# Loop_Schematic_r1_1_easyeda.net
KiCad netlist of a schematic drawn in EasyEDA
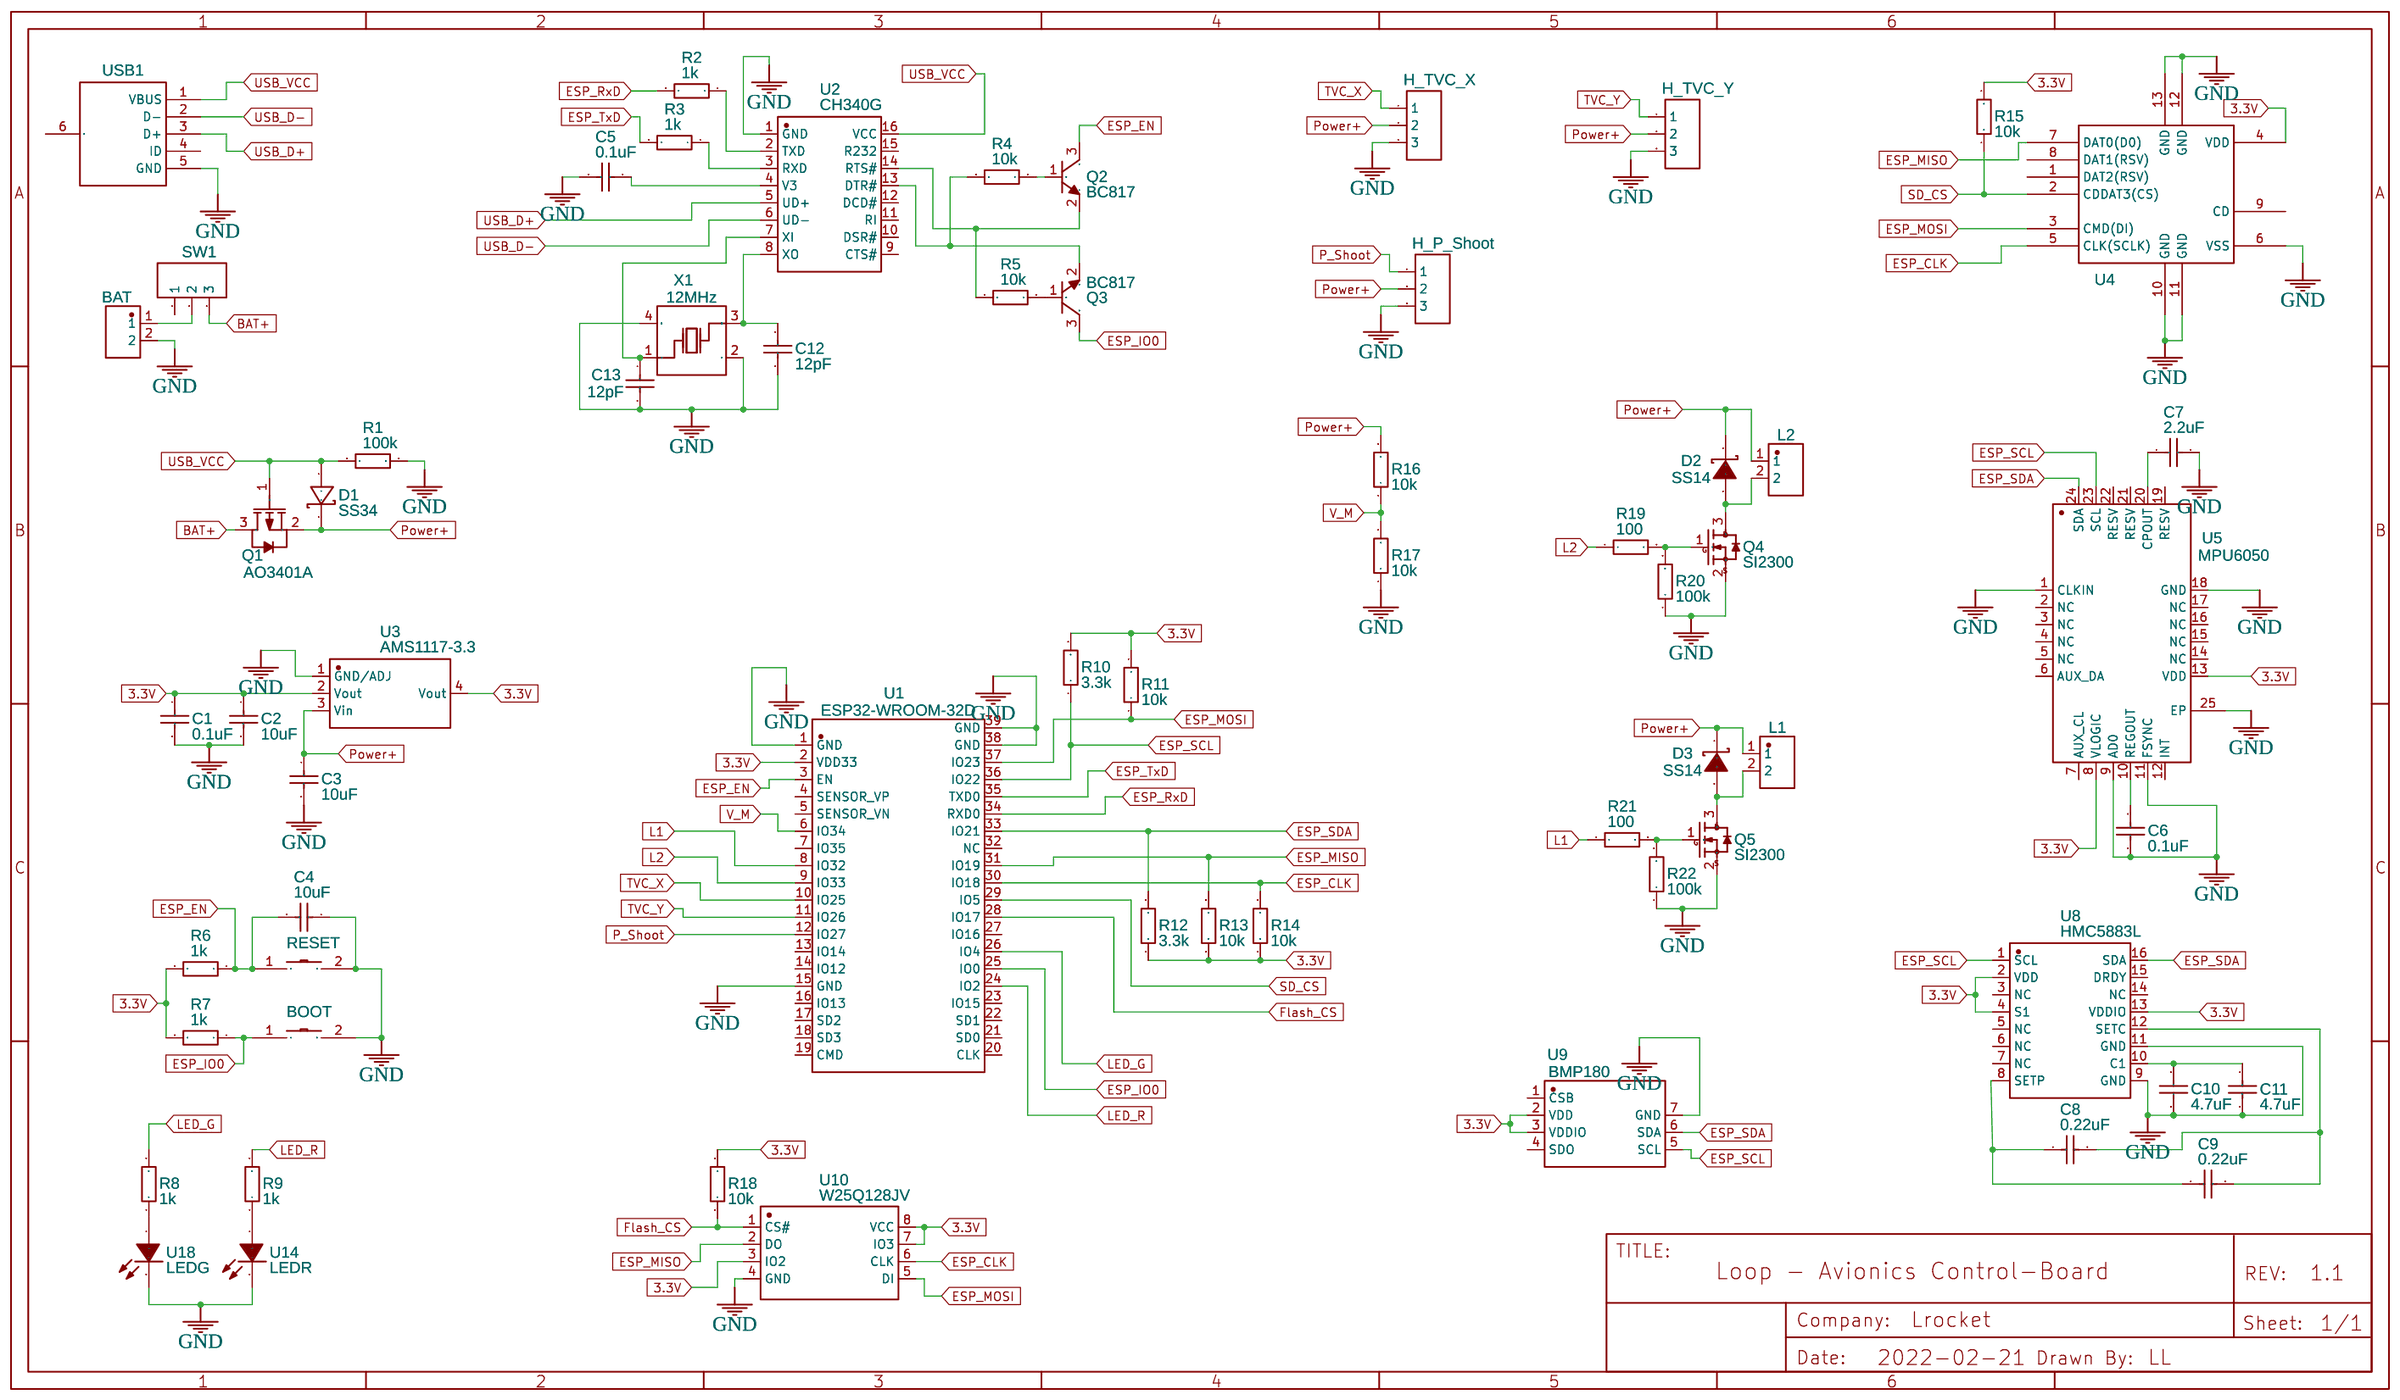
[diagram p0: schematic sheet]

(export (version "E")
  (design (tool "Eeschema 10.0.6"))
  (components
    (comp (ref "BAT")
      (value "XY308-2.54-2P")
      (fields (field (name "BOM_Supplier Part") "C557685"))
      (libsource (lib "") (part "XY308-2.54-2P_1"))
    )
    (comp (ref "BOOT")
      (value "TS-1101-C-W")
      (fields (field (name "BOM_Supplier Part") "C318938"))
      (libsource (lib "") (part "TS-1101-C-W_1"))
    )
    (comp (ref "C1")
      (value "0.1uF")
      (fields
        (field (name "BOM_Manufacturer Part") "CC0603KRX7R9BB103")
        (field (name "BOM_Supplier Part") "C100042")
      )
      (libsource (lib "") (part "CC0603KRX7R9BB103"))
    )
    (comp (ref "C2")
      (value "10uF")
      (fields
        (field (name "BOM_Manufacturer Part") "CC0603KRX7R9BB103")
        (field (name "BOM_Supplier Part") "C100042")
      )
      (libsource (lib "") (part "CC0603KRX7R9BB103"))
    )
    (comp (ref "C3")
      (value "10uF")
      (fields
        (field (name "BOM_Manufacturer Part") "CC0603KRX7R9BB103")
        (field (name "BOM_Supplier Part") "C100042")
      )
      (libsource (lib "") (part "CC0603KRX7R9BB103"))
    )
    (comp (ref "C4")
      (value "10uF")
      (fields
        (field (name "BOM_Manufacturer Part") "CC0603KRX7R9BB103")
        (field (name "BOM_Supplier Part") "C100042")
      )
      (libsource (lib "") (part "CC0603KRX7R9BB103_2"))
    )
    (comp (ref "C5")
      (value "0.1uF")
      (fields
        (field (name "BOM_Manufacturer Part") "CC0603KRX7R9BB103")
        (field (name "BOM_Supplier Part") "C100042")
      )
      (libsource (lib "") (part "CC0603KRX7R9BB103_2"))
    )
    (comp (ref "C6")
      (value "0.1uF")
      (fields
        (field (name "BOM_Manufacturer Part") "CC0603KRX7R9BB103")
        (field (name "BOM_Supplier Part") "C100042")
      )
      (libsource (lib "") (part "CC0603KRX7R9BB103_3"))
    )
    (comp (ref "C7")
      (value "2.2uF")
      (fields
        (field (name "BOM_Manufacturer Part") "CC0603KRX7R9BB103")
        (field (name "BOM_Supplier Part") "C100042")
      )
      (libsource (lib "") (part "CC0603KRX7R9BB103_1"))
    )
    (comp (ref "C8")
      (value "0.22uF")
      (fields
        (field (name "BOM_Manufacturer Part") "CC0603KRX7R9BB103")
        (field (name "BOM_Supplier Part") "C100042")
      )
      (libsource (lib "") (part "CC0603KRX7R9BB103_1"))
    )
    (comp (ref "C9")
      (value "0.22uF")
      (fields
        (field (name "BOM_Manufacturer Part") "DLC1.5P-C0805")
        (field (name "BOM_Supplier Part") "C9900002366")
      )
      (libsource (lib "") (part "DLC1.5P-C0805_1"))
    )
    (comp (ref "C10")
      (value "4.7uF")
      (fields
        (field (name "BOM_Manufacturer Part") "CC0603KRX7R9BB103")
        (field (name "BOM_Supplier Part") "C100042")
      )
      (libsource (lib "") (part "CC0603KRX7R9BB103"))
    )
    (comp (ref "C11")
      (value "4.7uF")
      (fields
        (field (name "BOM_Manufacturer Part") "DLC1.5P-C0805")
        (field (name "BOM_Supplier Part") "C9900002366")
      )
      (libsource (lib "") (part "DLC1.5P-C0805"))
    )
    (comp (ref "C12")
      (value "12pF")
      (fields
        (field (name "BOM_Manufacturer Part") "CC0603KRX7R9BB103")
        (field (name "BOM_Supplier Part") "C100042")
      )
      (libsource (lib "") (part "CC0603KRX7R9BB103"))
    )
    (comp (ref "C13")
      (value "12pF")
      (fields
        (field (name "BOM_Manufacturer Part") "CC0603KRX7R9BB103")
        (field (name "BOM_Supplier Part") "C100042")
      )
      (libsource (lib "") (part "CC0603KRX7R9BB103"))
    )
    (comp (ref "D1")
      (value "SS34")
      (fields (field (name "BOM_Supplier Part") "C8678"))
      (libsource (lib "") (part "SS34_C8678"))
    )
    (comp (ref "D2")
      (value "SS14")
      (fields (field (name "BOM_Supplier Part") "C2480"))
      (libsource (lib "") (part "SS14"))
    )
    (comp (ref "D3")
      (value "SS14")
      (fields (field (name "BOM_Supplier Part") "C2480"))
      (libsource (lib "") (part "SS14"))
    )
    (comp (ref "L1")
      (value "XY308-2.54-2P")
      (fields (field (name "BOM_Supplier Part") "C557685"))
      (libsource (lib "") (part "XY308-2.54-2P"))
    )
    (comp (ref "L2")
      (value "XY308-2.54-2P")
      (fields (field (name "BOM_Supplier Part") "C557685"))
      (libsource (lib "") (part "XY308-2.54-2P"))
    )
    (comp (ref "P_SHOOT")
      (value "H_P_Shoot")
      (fields
        (field (name "BOM_Manufacturer Part") "Header2.54mm 1*3P")
        (field (name "BOM_Supplier Part") "C49257")
      )
      (libsource (lib "") (part "Header-Male-2.54_1x3_1"))
    )
    (comp (ref "Q1")
      (value "AO3401A")
      (fields (field (name "BOM_Supplier Part") "C15127"))
      (libsource (lib "") (part "AO3401A"))
    )
    (comp (ref "Q2")
      (value "BC817")
      (fields (field (name "BOM_Manufacturer Part") "BC817-25") (field (name "BOM_Supplier Part") "C8588"))
      (libsource (lib "") (part "BC817-25_1"))
    )
    (comp (ref "Q3")
      (value "BC817")
      (fields (field (name "BOM_Manufacturer Part") "BC817-25") (field (name "BOM_Supplier Part") "C8588"))
      (libsource (lib "") (part "BC817-25"))
    )
    (comp (ref "Q4")
      (value "SI2300")
      (fields (field (name "BOM_Supplier Part") "C181085"))
      (libsource (lib "") (part "SI2300"))
    )
    (comp (ref "Q5")
      (value "SI2300")
      (fields (field (name "BOM_Supplier Part") "C181085"))
      (libsource (lib "") (part "SI2300"))
    )
    (comp (ref "R1")
      (value "100k")
      (fields
        (field (name "BOM_Manufacturer Part") "TR0603B10KP05250.1W")
        (field (name "BOM_Supplier Part") "C188363")
      )
      (libsource (lib "") (part "TR0603B10KP05250.1W_2"))
    )
    (comp (ref "R2")
      (value "1k")
      (fields
        (field (name "BOM_Manufacturer Part") "TR0603B10KP05250.1W")
        (field (name "BOM_Supplier Part") "C188363")
      )
      (libsource (lib "") (part "TR0603B10KP05250.1W_2"))
    )
    (comp (ref "R3")
      (value "1k")
      (fields
        (field (name "BOM_Manufacturer Part") "TR0603B10KP05250.1W")
        (field (name "BOM_Supplier Part") "C188363")
      )
      (libsource (lib "") (part "TR0603B10KP05250.1W_2"))
    )
    (comp (ref "R4")
      (value "10k")
      (fields
        (field (name "BOM_Manufacturer Part") "TR0603B10KP05250.1W")
        (field (name "BOM_Supplier Part") "C188363")
      )
      (libsource (lib "") (part "TR0603B10KP05250.1W_2"))
    )
    (comp (ref "R5")
      (value "10k")
      (fields
        (field (name "BOM_Manufacturer Part") "TR0603B10KP05250.1W")
        (field (name "BOM_Supplier Part") "C188363")
      )
      (libsource (lib "") (part "TR0603B10KP05250.1W_2"))
    )
    (comp (ref "R6")
      (value "1k")
      (fields
        (field (name "BOM_Manufacturer Part") "TR0603B10KP05250.1W")
        (field (name "BOM_Supplier Part") "C188363")
      )
      (libsource (lib "") (part "TR0603B10KP05250.1W_2"))
    )
    (comp (ref "R7")
      (value "1k")
      (fields
        (field (name "BOM_Manufacturer Part") "TR0603B10KP05250.1W")
        (field (name "BOM_Supplier Part") "C188363")
      )
      (libsource (lib "") (part "TR0603B10KP05250.1W_2"))
    )
    (comp (ref "R8")
      (value "1k")
      (fields
        (field (name "BOM_Manufacturer Part") "TR0603B10KP05250.1W")
        (field (name "BOM_Supplier Part") "C188363")
      )
      (libsource (lib "") (part "TR0603B10KP05250.1W"))
    )
    (comp (ref "R9")
      (value "1k")
      (fields
        (field (name "BOM_Manufacturer Part") "TR0603B10KP05250.1W")
        (field (name "BOM_Supplier Part") "C188363")
      )
      (libsource (lib "") (part "TR0603B10KP05250.1W"))
    )
    (comp (ref "R10")
      (value "3.3k")
      (fields
        (field (name "BOM_Manufacturer Part") "TR0603B10KP05250.1W")
        (field (name "BOM_Supplier Part") "C188363")
      )
      (libsource (lib "") (part "TR0603B10KP05250.1W"))
    )
    (comp (ref "R11")
      (value "10k")
      (fields
        (field (name "BOM_Manufacturer Part") "TR0603B10KP05250.1W")
        (field (name "BOM_Supplier Part") "C188363")
      )
      (libsource (lib "") (part "TR0603B10KP05250.1W"))
    )
    (comp (ref "R12")
      (value "3.3k")
      (fields
        (field (name "BOM_Manufacturer Part") "TR0603B10KP05250.1W")
        (field (name "BOM_Supplier Part") "C188363")
      )
      (libsource (lib "") (part "TR0603B10KP05250.1W"))
    )
    (comp (ref "R13")
      (value "10k")
      (fields
        (field (name "BOM_Manufacturer Part") "TR0603B10KP05250.1W")
        (field (name "BOM_Supplier Part") "C188363")
      )
      (libsource (lib "") (part "TR0603B10KP05250.1W"))
    )
    (comp (ref "R14")
      (value "10k")
      (fields
        (field (name "BOM_Manufacturer Part") "TR0603B10KP05250.1W")
        (field (name "BOM_Supplier Part") "C188363")
      )
      (libsource (lib "") (part "TR0603B10KP05250.1W"))
    )
    (comp (ref "R15")
      (value "10k")
      (fields
        (field (name "BOM_Manufacturer Part") "TR0603B10KP05250.1W")
        (field (name "BOM_Supplier Part") "C188363")
      )
      (libsource (lib "") (part "TR0603B10KP05250.1W"))
    )
    (comp (ref "R16")
      (value "10k")
      (fields
        (field (name "BOM_Manufacturer Part") "TR0603B10KP05250.1W")
        (field (name "BOM_Supplier Part") "C188363")
      )
      (libsource (lib "") (part "TR0603B10KP05250.1W"))
    )
    (comp (ref "R17")
      (value "10k")
      (fields
        (field (name "BOM_Manufacturer Part") "TR0603B10KP05250.1W")
        (field (name "BOM_Supplier Part") "C188363")
      )
      (libsource (lib "") (part "TR0603B10KP05250.1W"))
    )
    (comp (ref "R18")
      (value "10k")
      (fields
        (field (name "BOM_Manufacturer Part") "TR0603B10KP05250.1W")
        (field (name "BOM_Supplier Part") "C188363")
      )
      (libsource (lib "") (part "TR0603B10KP05250.1W"))
    )
    (comp (ref "R19")
      (value "100")
      (fields
        (field (name "BOM_Manufacturer Part") "TR0603B10KP05250.1W")
        (field (name "BOM_Supplier Part") "C188363")
      )
      (libsource (lib "") (part "TR0603B10KP05250.1W_1"))
    )
    (comp (ref "R20")
      (value "100k")
      (fields
        (field (name "BOM_Manufacturer Part") "TR0603B10KP05250.1W")
        (field (name "BOM_Supplier Part") "C188363")
      )
      (libsource (lib "") (part "TR0603B10KP05250.1W"))
    )
    (comp (ref "R21")
      (value "100")
      (fields
        (field (name "BOM_Manufacturer Part") "TR0603B10KP05250.1W")
        (field (name "BOM_Supplier Part") "C188363")
      )
      (libsource (lib "") (part "TR0603B10KP05250.1W_1"))
    )
    (comp (ref "R22")
      (value "100k")
      (fields
        (field (name "BOM_Manufacturer Part") "TR0603B10KP05250.1W")
        (field (name "BOM_Supplier Part") "C188363")
      )
      (libsource (lib "") (part "TR0603B10KP05250.1W"))
    )
    (comp (ref "RESET")
      (value "TS-1101-C-W")
      (fields (field (name "BOM_Supplier Part") "C318938"))
      (libsource (lib "") (part "TS-1101-C-W"))
    )
    (comp (ref "SW1")
      (value "SW1")
      (fields
        (field (name "BOM_Manufacturer Part") "Header2.54mm 1*3P")
        (field (name "BOM_Supplier Part") "C49257")
      )
      (libsource (lib "") (part "Header-Male-2.54_1x3"))
    )
    (comp (ref "TVC_X")
      (value "H_TVC_X")
      (fields
        (field (name "BOM_Manufacturer Part") "Header2.54mm 1*3P")
        (field (name "BOM_Supplier Part") "C49257")
      )
      (libsource (lib "") (part "Header-Male-2.54_1x3_3"))
    )
    (comp (ref "TVC_Y")
      (value "H_TVC_Y")
      (fields
        (field (name "BOM_Manufacturer Part") "Header2.54mm 1*3P")
        (field (name "BOM_Supplier Part") "C49257")
      )
      (libsource (lib "") (part "Header-Male-2.54_1x3_2"))
    )
    (comp (ref "U1")
      (value "ESP32-WROOM-32D")
      (fields (field (name "BOM_Supplier Part") "C473012"))
      (libsource (lib "") (part "ESP32-WROOM-32D"))
    )
    (comp (ref "U2")
      (value "CH340G")
      (fields (field (name "BOM_Supplier Part") "C14267"))
      (libsource (lib "") (part "CH340G"))
    )
    (comp (ref "U3")
      (value "AMS1117-3.3")
      (fields (field (name "BOM_Supplier Part") "C6186"))
      (libsource (lib "") (part "AMS1117-3.3"))
    )
    (comp (ref "U4")
      (value "TF-01A")
      (fields (field (name "BOM_Supplier Part") "C91145"))
      (libsource (lib "") (part "TF-01A"))
    )
    (comp (ref "U5")
      (value "MPU6050")
      (fields
        (field (name "BOM_Manufacturer Part") "MPU6050-YJLTY")
        (field (name "BOM_Supplier Part") "C2912107")
      )
      (libsource (lib "") (part "MPU6050-YJLTY"))
    )
    (comp (ref "U8")
      (value "HMC5883L")
      (fields (field (name "BOM_Supplier Part") "C2859540"))
      (libsource (lib "") (part "HMC5883L"))
    )
    (comp (ref "U9")
      (value "BMP180")
      (fields (field (name "BOM_Supplier Part") "C438474"))
      (libsource (lib "") (part "BMP180"))
    )
    (comp (ref "U10")
      (value "W25Q128JV")
      (fields
        (field (name "BOM_Manufacturer Part") "W25Q128JVSIQTR")
        (field (name "BOM_Supplier Part") "C97521")
      )
      (libsource (lib "") (part "W25Q128JVSIQTR"))
    )
    (comp (ref "U14")
      (value "LEDR")
      (fields (field (name "BOM_Manufacturer Part") "SZYY0603W") (field (name "BOM_Supplier Part") "C434422"))
      (libsource (lib "") (part "SZYY0603W"))
    )
    (comp (ref "U18")
      (value "LEDG")
      (fields (field (name "BOM_Manufacturer Part") "SZYY0603W") (field (name "BOM_Supplier Part") "C434422"))
      (libsource (lib "") (part "SZYY0603W"))
    )
    (comp (ref "USB1")
      (value "USB1")
      (fields
        (field (name "BOM_Manufacturer Part") "U254-051T-4BH83-S1S")
        (field (name "BOM_Supplier Part") "C319160")
      )
      (libsource (lib "") (part "U254-051T-4BH83-S1S"))
    )
    (comp (ref "X1")
      (value "12MHz")
      (fields
        (field (name "BOM_Manufacturer Part") "X322512MOB4SI")
        (field (name "BOM_Supplier Part") "C70565")
      )
      (libsource (lib "") (part "X322512MOB4SI"))
    )
  )
  (nets
    (net (code "1") (name "3.3V") (class "Default")
      (node (ref "C1") (pin "1") (pinfunction "1_1") (pintype "input"))
      (node (ref "C2") (pin "1") (pinfunction "1_1") (pintype "input"))
      (node (ref "R10") (pin "2") (pinfunction "2_2") (pintype "unspecified"))
      (node (ref "R11") (pin "2") (pinfunction "2_2") (pintype "unspecified"))
      (node (ref "R12") (pin "1") (pinfunction "1_1") (pintype "unspecified"))
      (node (ref "R13") (pin "1") (pinfunction "1_1") (pintype "unspecified"))
      (node (ref "R14") (pin "1") (pinfunction "1_1") (pintype "unspecified"))
      (node (ref "R15") (pin "2") (pinfunction "2_2") (pintype "unspecified"))
      (node (ref "R18") (pin "2") (pinfunction "2_2") (pintype "unspecified"))
      (node (ref "R6") (pin "2") (pinfunction "2_2") (pintype "unspecified"))
      (node (ref "R7") (pin "2") (pinfunction "2_2") (pintype "unspecified"))
      (node (ref "U1") (pin "2") (pinfunction "VDD33_2") (pintype "unspecified"))
      (node (ref "U10") (pin "3") (pinfunction "IO2_3") (pintype "unspecified"))
      (node (ref "U10") (pin "7") (pinfunction "IO3_7") (pintype "unspecified"))
      (node (ref "U10") (pin "8") (pinfunction "VCC_8") (pintype "unspecified"))
      (node (ref "U3") (pin "2") (pinfunction "Vout_2") (pintype "unspecified"))
      (node (ref "U3") (pin "4") (pinfunction "Vout_4") (pintype "unspecified"))
      (node (ref "U4") (pin "4") (pinfunction "VDD_4") (pintype "input"))
      (node (ref "U5") (pin "13") (pinfunction "VDD_13") (pintype "unspecified"))
      (node (ref "U5") (pin "8") (pinfunction "VLOGIC_8") (pintype "unspecified"))
      (node (ref "U8") (pin "13") (pinfunction "VDDIO_13") (pintype "unspecified"))
      (node (ref "U8") (pin "2") (pinfunction "VDD_2") (pintype "unspecified"))
      (node (ref "U8") (pin "4") (pinfunction "S1_4") (pintype "unspecified"))
      (node (ref "U9") (pin "2") (pinfunction "VDD_2") (pintype "unspecified"))
      (node (ref "U9") (pin "3") (pinfunction "VDDIO_3") (pintype "unspecified"))
    )
    (net (code "2") (name "BAT+") (class "Default")
      (node (ref "Q1") (pin "3") (pinfunction "D_3") (pintype "unspecified"))
      (node (ref "SW1") (pin "3") (pinfunction "3_3") (pintype "input"))
    )
    (net (code "3") (name "ESP_CLK") (class "Default")
      (node (ref "R14") (pin "2") (pinfunction "2_2") (pintype "unspecified"))
      (node (ref "U1") (pin "30") (pinfunction "IO18_30") (pintype "unspecified"))
      (node (ref "U10") (pin "6") (pinfunction "CLK_6") (pintype "unspecified"))
      (node (ref "U4") (pin "5") (pinfunction "CLK(SCLK)_5") (pintype "input"))
    )
    (net (code "4") (name "ESP_EN") (class "Default")
      (node (ref "C4") (pin "2") (pinfunction "2_2") (pintype "input"))
      (node (ref "Q2") (pin "3") (pinfunction "C_3") (pintype "unspecified"))
      (node (ref "R6") (pin "1") (pinfunction "1_1") (pintype "unspecified"))
      (node (ref "RESET") (pin "1") (pinfunction "1_1") (pintype "unspecified"))
      (node (ref "U1") (pin "3") (pinfunction "EN_3") (pintype "unspecified"))
    )
    (net (code "5") (name "ESP_IO0") (class "Default")
      (node (ref "BOOT") (pin "1") (pinfunction "1_1") (pintype "unspecified"))
      (node (ref "Q3") (pin "3") (pinfunction "C_3") (pintype "unspecified"))
      (node (ref "R7") (pin "1") (pinfunction "1_1") (pintype "unspecified"))
      (node (ref "U1") (pin "25") (pinfunction "IO0_25") (pintype "unspecified"))
    )
    (net (code "6") (name "ESP_MISO") (class "Default")
      (node (ref "R13") (pin "2") (pinfunction "2_2") (pintype "unspecified"))
      (node (ref "U1") (pin "31") (pinfunction "IO19_31") (pintype "unspecified"))
      (node (ref "U10") (pin "2") (pinfunction "DO_2") (pintype "unspecified"))
      (node (ref "U4") (pin "7") (pinfunction "DAT0(D0)_7") (pintype "bidirectional"))
    )
    (net (code "7") (name "ESP_MOSI") (class "Default")
      (node (ref "R11") (pin "1") (pinfunction "1_1") (pintype "unspecified"))
      (node (ref "U1") (pin "37") (pinfunction "IO23_37") (pintype "unspecified"))
      (node (ref "U10") (pin "5") (pinfunction "DI_5") (pintype "unspecified"))
      (node (ref "U4") (pin "3") (pinfunction "CMD(DI)_3") (pintype "input"))
    )
    (net (code "8") (name "ESP_RxD") (class "Default")
      (node (ref "R2") (pin "2") (pinfunction "2_2") (pintype "unspecified"))
      (node (ref "U1") (pin "34") (pinfunction "RXD0_34") (pintype "unspecified"))
    )
    (net (code "9") (name "ESP_SCL") (class "Default")
      (node (ref "R10") (pin "1") (pinfunction "1_1") (pintype "unspecified"))
      (node (ref "U1") (pin "36") (pinfunction "IO22_36") (pintype "unspecified"))
      (node (ref "U5") (pin "23") (pinfunction "SCL_23") (pintype "unspecified"))
      (node (ref "U8") (pin "1") (pinfunction "SCL_1") (pintype "unspecified"))
      (node (ref "U9") (pin "5") (pinfunction "SCL_5") (pintype "unspecified"))
    )
    (net (code "10") (name "ESP_SDA") (class "Default")
      (node (ref "R12") (pin "2") (pinfunction "2_2") (pintype "unspecified"))
      (node (ref "U1") (pin "33") (pinfunction "IO21_33") (pintype "unspecified"))
      (node (ref "U5") (pin "24") (pinfunction "SDA_24") (pintype "unspecified"))
      (node (ref "U8") (pin "16") (pinfunction "SDA_16") (pintype "unspecified"))
      (node (ref "U9") (pin "6") (pinfunction "SDA_6") (pintype "unspecified"))
    )
    (net (code "11") (name "ESP_TxD") (class "Default")
      (node (ref "R3") (pin "2") (pinfunction "2_2") (pintype "unspecified"))
      (node (ref "U1") (pin "35") (pinfunction "TXD0_35") (pintype "unspecified"))
    )
    (net (code "12") (name "Flash_CS") (class "Default")
      (node (ref "R18") (pin "1") (pinfunction "1_1") (pintype "unspecified"))
      (node (ref "U1") (pin "28") (pinfunction "IO17_28") (pintype "unspecified"))
      (node (ref "U10") (pin "1") (pinfunction "CS#_1") (pintype "unspecified"))
    )
    (net (code "13") (name "GND") (class "Default")
      (node (ref "BAT") (pin "2") (pinfunction "2_2") (pintype "unspecified"))
      (node (ref "BOOT") (pin "2") (pinfunction "2_2") (pintype "unspecified"))
      (node (ref "C1") (pin "2") (pinfunction "2_2") (pintype "input"))
      (node (ref "C10") (pin "2") (pinfunction "2_2") (pintype "input"))
      (node (ref "C11") (pin "2") (pinfunction "2_2") (pintype "input"))
      (node (ref "C12") (pin "2") (pinfunction "2_2") (pintype "input"))
      (node (ref "C13") (pin "2") (pinfunction "2_2") (pintype "input"))
      (node (ref "C2") (pin "2") (pinfunction "2_2") (pintype "input"))
      (node (ref "C3") (pin "2") (pinfunction "2_2") (pintype "input"))
      (node (ref "C4") (pin "1") (pinfunction "1_1") (pintype "input"))
      (node (ref "C5") (pin "2") (pinfunction "2_2") (pintype "input"))
      (node (ref "C6") (pin "1") (pinfunction "1_1") (pintype "input"))
      (node (ref "C7") (pin "2") (pinfunction "2_2") (pintype "input"))
      (node (ref "P_SHOOT") (pin "3") (pinfunction "3_3") (pintype "input"))
      (node (ref "Q4") (pin "2") (pinfunction "S_2") (pintype "unspecified"))
      (node (ref "Q5") (pin "2") (pinfunction "S_2") (pintype "unspecified"))
      (node (ref "R1") (pin "1") (pinfunction "1_1") (pintype "unspecified"))
      (node (ref "R17") (pin "1") (pinfunction "1_1") (pintype "unspecified"))
      (node (ref "R20") (pin "1") (pinfunction "1_1") (pintype "unspecified"))
      (node (ref "R22") (pin "1") (pinfunction "1_1") (pintype "unspecified"))
      (node (ref "RESET") (pin "2") (pinfunction "2_2") (pintype "unspecified"))
      (node (ref "TVC_X") (pin "3") (pinfunction "3_3") (pintype "input"))
      (node (ref "TVC_Y") (pin "3") (pinfunction "3_3") (pintype "input"))
      (node (ref "U1") (pin "1") (pinfunction "GND_1") (pintype "unspecified"))
      (node (ref "U1") (pin "15") (pinfunction "GND_15") (pintype "unspecified"))
      (node (ref "U1") (pin "38") (pinfunction "GND_38") (pintype "unspecified"))
      (node (ref "U1") (pin "39") (pinfunction "GND_39") (pintype "unspecified"))
      (node (ref "U10") (pin "4") (pinfunction "GND_4") (pintype "unspecified"))
      (node (ref "U14") (pin "2") (pinfunction "-_2") (pintype "unspecified"))
      (node (ref "U18") (pin "2") (pinfunction "-_2") (pintype "unspecified"))
      (node (ref "U2") (pin "1") (pinfunction "GND_1") (pintype "unspecified"))
      (node (ref "U3") (pin "1") (pinfunction "GND/ADJ_1") (pintype "unspecified"))
      (node (ref "U4") (pin "10") (pinfunction "GND_10") (pintype "input"))
      (node (ref "U4") (pin "11") (pinfunction "GND_11") (pintype "input"))
      (node (ref "U4") (pin "12") (pinfunction "GND_12") (pintype "input"))
      (node (ref "U4") (pin "13") (pinfunction "GND_13") (pintype "input"))
      (node (ref "U4") (pin "6") (pinfunction "VSS_6") (pintype "input"))
      (node (ref "U5") (pin "1") (pinfunction "CLKIN_1") (pintype "unspecified"))
      (node (ref "U5") (pin "11") (pinfunction "FSYNC_11") (pintype "unspecified"))
      (node (ref "U5") (pin "18") (pinfunction "GND_18") (pintype "unspecified"))
      (node (ref "U5") (pin "25") (pinfunction "EP_25") (pintype "unspecified"))
      (node (ref "U5") (pin "9") (pinfunction "AD0_9") (pintype "unspecified"))
      (node (ref "U8") (pin "11") (pinfunction "GND_11") (pintype "unspecified"))
      (node (ref "U8") (pin "9") (pinfunction "GND_9") (pintype "unspecified"))
      (node (ref "U9") (pin "7") (pinfunction "GND_7") (pintype "unspecified"))
      (node (ref "USB1") (pin "5") (pinfunction "GND_5") (pintype "input"))
      (node (ref "X1") (pin "2") (pinfunction "GND_2") (pintype "unspecified"))
      (node (ref "X1") (pin "4") (pinfunction "GND_4") (pintype "unspecified"))
    )
    (net (code "14") (name "L1") (class "Default")
      (node (ref "R21") (pin "1") (pinfunction "1_1") (pintype "unspecified"))
      (node (ref "U1") (pin "8") (pinfunction "IO32_8") (pintype "unspecified"))
    )
    (net (code "15") (name "L2") (class "Default")
      (node (ref "R19") (pin "1") (pinfunction "1_1") (pintype "unspecified"))
      (node (ref "U1") (pin "9") (pinfunction "IO33_9") (pintype "unspecified"))
    )
    (net (code "16") (name "LED_G") (class "Default")
      (node (ref "R8") (pin "2") (pinfunction "2_2") (pintype "unspecified"))
      (node (ref "U1") (pin "26") (pinfunction "IO4_26") (pintype "unspecified"))
    )
    (net (code "17") (name "LED_R") (class "Default")
      (node (ref "R9") (pin "2") (pinfunction "2_2") (pintype "unspecified"))
      (node (ref "U1") (pin "24") (pinfunction "IO2_24") (pintype "unspecified"))
    )
    (net (code "18") (name "Net-(BAT-Pad1)") (class "Default")
      (node (ref "BAT") (pin "1") (pinfunction "1_1") (pintype "unspecified"))
      (node (ref "SW1") (pin "2") (pinfunction "2_2") (pintype "input"))
    )
    (net (code "19") (name "Net-(D2-A)") (class "Default")
      (node (ref "D2") (pin "2") (pinfunction "A_2") (pintype "unspecified"))
      (node (ref "L2") (pin "2") (pinfunction "2_2") (pintype "unspecified"))
      (node (ref "Q4") (pin "3") (pinfunction "D_3") (pintype "unspecified"))
    )
    (net (code "20") (name "Net-(D3-A)") (class "Default")
      (node (ref "D3") (pin "2") (pinfunction "A_2") (pintype "unspecified"))
      (node (ref "L1") (pin "2") (pinfunction "2_2") (pintype "unspecified"))
      (node (ref "Q5") (pin "3") (pinfunction "D_3") (pintype "unspecified"))
    )
    (net (code "21") (name "Net-(Q2-B)") (class "Default")
      (node (ref "Q2") (pin "1") (pinfunction "B_1") (pintype "unspecified"))
      (node (ref "R4") (pin "1") (pinfunction "1_1") (pintype "unspecified"))
    )
    (net (code "22") (name "Net-(Q2-E)") (class "Default")
      (node (ref "Q2") (pin "2") (pinfunction "E_2") (pintype "unspecified"))
      (node (ref "R5") (pin "2") (pinfunction "2_2") (pintype "unspecified"))
      (node (ref "U2") (pin "14") (pinfunction "RTS#_14") (pintype "unspecified"))
    )
    (net (code "23") (name "Net-(Q3-B)") (class "Default")
      (node (ref "Q3") (pin "1") (pinfunction "B_1") (pintype "unspecified"))
      (node (ref "R5") (pin "1") (pinfunction "1_1") (pintype "unspecified"))
    )
    (net (code "24") (name "Net-(Q3-E)") (class "Default")
      (node (ref "Q3") (pin "2") (pinfunction "E_2") (pintype "unspecified"))
      (node (ref "R4") (pin "2") (pinfunction "2_2") (pintype "unspecified"))
      (node (ref "U2") (pin "13") (pinfunction "DTR#_13") (pintype "unspecified"))
    )
    (net (code "25") (name "Net-(Q4-G)") (class "Default")
      (node (ref "Q4") (pin "1") (pinfunction "G_1") (pintype "unspecified"))
      (node (ref "R19") (pin "2") (pinfunction "2_2") (pintype "unspecified"))
      (node (ref "R20") (pin "2") (pinfunction "2_2") (pintype "unspecified"))
    )
    (net (code "26") (name "Net-(Q5-G)") (class "Default")
      (node (ref "Q5") (pin "1") (pinfunction "G_1") (pintype "unspecified"))
      (node (ref "R21") (pin "2") (pinfunction "2_2") (pintype "unspecified"))
      (node (ref "R22") (pin "2") (pinfunction "2_2") (pintype "unspecified"))
    )
    (net (code "27") (name "Net-(U2-RXD)") (class "Default")
      (node (ref "R3") (pin "1") (pinfunction "1_1") (pintype "unspecified"))
      (node (ref "U2") (pin "3") (pinfunction "RXD_3") (pintype "unspecified"))
    )
    (net (code "28") (name "Net-(U2-TXD)") (class "Default")
      (node (ref "R2") (pin "1") (pinfunction "1_1") (pintype "unspecified"))
      (node (ref "U2") (pin "2") (pinfunction "TXD_2") (pintype "unspecified"))
    )
    (net (code "29") (name "Net-(U2-V3)") (class "Default")
      (node (ref "C5") (pin "1") (pinfunction "1_1") (pintype "input"))
      (node (ref "U2") (pin "4") (pinfunction "V3_4") (pintype "unspecified"))
    )
    (net (code "30") (name "Net-(U2-XI)") (class "Default")
      (node (ref "C13") (pin "1") (pinfunction "1_1") (pintype "input"))
      (node (ref "U2") (pin "7") (pinfunction "XI_7") (pintype "unspecified"))
      (node (ref "X1") (pin "1") (pinfunction "OSC1_1") (pintype "unspecified"))
    )
    (net (code "31") (name "Net-(U2-XO)") (class "Default")
      (node (ref "C12") (pin "1") (pinfunction "1_1") (pintype "input"))
      (node (ref "U2") (pin "8") (pinfunction "XO_8") (pintype "unspecified"))
      (node (ref "X1") (pin "3") (pinfunction "OSC2_3") (pintype "unspecified"))
    )
    (net (code "32") (name "Net-(U5-CPOUT)") (class "Default")
      (node (ref "C7") (pin "1") (pinfunction "1_1") (pintype "input"))
      (node (ref "U5") (pin "20") (pinfunction "CPOUT_20") (pintype "unspecified"))
    )
    (net (code "33") (name "Net-(U5-REGOUT)") (class "Default")
      (node (ref "C6") (pin "2") (pinfunction "2_2") (pintype "input"))
      (node (ref "U5") (pin "10") (pinfunction "REGOUT_10") (pintype "unspecified"))
    )
    (net (code "34") (name "Net-(U8-C1)") (class "Default")
      (node (ref "C10") (pin "1") (pinfunction "1_1") (pintype "input"))
      (node (ref "C11") (pin "1") (pinfunction "1_1") (pintype "input"))
      (node (ref "U8") (pin "10") (pinfunction "C1_10") (pintype "unspecified"))
    )
    (net (code "35") (name "Net-(U8-SETC)") (class "Default")
      (node (ref "C8") (pin "2") (pinfunction "2_2") (pintype "input"))
      (node (ref "C9") (pin "2") (pinfunction "2_2") (pintype "input"))
      (node (ref "U8") (pin "12") (pinfunction "SETC_12") (pintype "unspecified"))
    )
    (net (code "36") (name "Net-(U8-SETP)") (class "Default")
      (node (ref "C8") (pin "1") (pinfunction "1_1") (pintype "input"))
      (node (ref "C9") (pin "1") (pinfunction "1_1") (pintype "input"))
      (node (ref "U8") (pin "8") (pinfunction "SETP_8") (pintype "unspecified"))
    )
    (net (code "37") (name "Net-(U14-+)") (class "Default")
      (node (ref "R9") (pin "1") (pinfunction "1_1") (pintype "unspecified"))
      (node (ref "U14") (pin "1") (pinfunction "+_1") (pintype "unspecified"))
    )
    (net (code "38") (name "Net-(U18-+)") (class "Default")
      (node (ref "R8") (pin "1") (pinfunction "1_1") (pintype "unspecified"))
      (node (ref "U18") (pin "1") (pinfunction "+_1") (pintype "unspecified"))
    )
    (net (code "39") (name "P_Shoot") (class "Default")
      (node (ref "P_SHOOT") (pin "1") (pinfunction "1_1") (pintype "input"))
      (node (ref "U1") (pin "12") (pinfunction "IO27_12") (pintype "unspecified"))
    )
    (net (code "40") (name "Power+") (class "Default")
      (node (ref "C3") (pin "1") (pinfunction "1_1") (pintype "input"))
      (node (ref "D1") (pin "1") (pinfunction "K_1") (pintype "unspecified"))
      (node (ref "D2") (pin "1") (pinfunction "K_1") (pintype "unspecified"))
      (node (ref "D3") (pin "1") (pinfunction "K_1") (pintype "unspecified"))
      (node (ref "L1") (pin "1") (pinfunction "1_1") (pintype "unspecified"))
      (node (ref "L2") (pin "1") (pinfunction "1_1") (pintype "unspecified"))
      (node (ref "P_SHOOT") (pin "2") (pinfunction "2_2") (pintype "input"))
      (node (ref "Q1") (pin "2") (pinfunction "S_2") (pintype "unspecified"))
      (node (ref "R16") (pin "2") (pinfunction "2_2") (pintype "unspecified"))
      (node (ref "TVC_X") (pin "2") (pinfunction "2_2") (pintype "input"))
      (node (ref "TVC_Y") (pin "2") (pinfunction "2_2") (pintype "input"))
      (node (ref "U3") (pin "3") (pinfunction "Vin_3") (pintype "unspecified"))
    )
    (net (code "41") (name "SD_CS") (class "Default")
      (node (ref "R15") (pin "1") (pinfunction "1_1") (pintype "unspecified"))
      (node (ref "U1") (pin "29") (pinfunction "IO5_29") (pintype "unspecified"))
      (node (ref "U4") (pin "2") (pinfunction "CDDAT3(CS)_2") (pintype "bidirectional"))
    )
    (net (code "42") (name "TVC_X") (class "Default")
      (node (ref "TVC_X") (pin "1") (pinfunction "1_1") (pintype "input"))
      (node (ref "U1") (pin "10") (pinfunction "IO25_10") (pintype "unspecified"))
    )
    (net (code "43") (name "TVC_Y") (class "Default")
      (node (ref "TVC_Y") (pin "1") (pinfunction "1_1") (pintype "input"))
      (node (ref "U1") (pin "11") (pinfunction "IO26_11") (pintype "unspecified"))
    )
    (net (code "44") (name "USB_D+") (class "Default")
      (node (ref "U2") (pin "5") (pinfunction "UD+_5") (pintype "unspecified"))
      (node (ref "USB1") (pin "3") (pinfunction "D+_3") (pintype "input"))
    )
    (net (code "45") (name "USB_D-") (class "Default")
      (node (ref "U2") (pin "6") (pinfunction "UD-_6") (pintype "unspecified"))
      (node (ref "USB1") (pin "2") (pinfunction "D-_2") (pintype "input"))
    )
    (net (code "46") (name "USB_VCC") (class "Default")
      (node (ref "D1") (pin "2") (pinfunction "A_2") (pintype "unspecified"))
      (node (ref "Q1") (pin "1") (pinfunction "G_1") (pintype "unspecified"))
      (node (ref "R1") (pin "2") (pinfunction "2_2") (pintype "unspecified"))
      (node (ref "U2") (pin "16") (pinfunction "VCC_16") (pintype "unspecified"))
      (node (ref "USB1") (pin "1") (pinfunction "VBUS_1") (pintype "input"))
    )
    (net (code "47") (name "V_M") (class "Default")
      (node (ref "R16") (pin "1") (pinfunction "1_1") (pintype "unspecified"))
      (node (ref "R17") (pin "2") (pinfunction "2_2") (pintype "unspecified"))
      (node (ref "U1") (pin "6") (pinfunction "IO34_6") (pintype "unspecified"))
    )
    (net (code "48") (name "unconnected-(SW1-Pad1)") (class "Default")
      (node (ref "SW1") (pin "1") (pinfunction "1_1") (pintype "input"))
    )
    (net (code "49") (name "unconnected-(U1-CLK-Pad20)") (class "Default")
      (node (ref "U1") (pin "20") (pinfunction "CLK_20") (pintype "unspecified"))
    )
    (net (code "50") (name "unconnected-(U1-CMD-Pad19)") (class "Default")
      (node (ref "U1") (pin "19") (pinfunction "CMD_19") (pintype "unspecified"))
    )
    (net (code "51") (name "unconnected-(U1-IO12-Pad14)") (class "Default")
      (node (ref "U1") (pin "14") (pinfunction "IO12_14") (pintype "unspecified"))
    )
    (net (code "52") (name "unconnected-(U1-IO13-Pad16)") (class "Default")
      (node (ref "U1") (pin "16") (pinfunction "IO13_16") (pintype "unspecified"))
    )
    (net (code "53") (name "unconnected-(U1-IO14-Pad13)") (class "Default")
      (node (ref "U1") (pin "13") (pinfunction "IO14_13") (pintype "unspecified"))
    )
    (net (code "54") (name "unconnected-(U1-IO15-Pad23)") (class "Default")
      (node (ref "U1") (pin "23") (pinfunction "IO15_23") (pintype "unspecified"))
    )
    (net (code "55") (name "unconnected-(U1-IO16-Pad27)") (class "Default")
      (node (ref "U1") (pin "27") (pinfunction "IO16_27") (pintype "unspecified"))
    )
    (net (code "56") (name "unconnected-(U1-IO35-Pad7)") (class "Default")
      (node (ref "U1") (pin "7") (pinfunction "IO35_7") (pintype "unspecified"))
    )
    (net (code "57") (name "unconnected-(U1-NC-Pad32)") (class "Default")
      (node (ref "U1") (pin "32") (pinfunction "NC_32") (pintype "unspecified"))
    )
    (net (code "58") (name "unconnected-(U1-SD0-Pad21)") (class "Default")
      (node (ref "U1") (pin "21") (pinfunction "SD0_21") (pintype "unspecified"))
    )
    (net (code "59") (name "unconnected-(U1-SD1-Pad22)") (class "Default")
      (node (ref "U1") (pin "22") (pinfunction "SD1_22") (pintype "unspecified"))
    )
    (net (code "60") (name "unconnected-(U1-SD2-Pad17)") (class "Default")
      (node (ref "U1") (pin "17") (pinfunction "SD2_17") (pintype "unspecified"))
    )
    (net (code "61") (name "unconnected-(U1-SD3-Pad18)") (class "Default")
      (node (ref "U1") (pin "18") (pinfunction "SD3_18") (pintype "unspecified"))
    )
    (net (code "62") (name "unconnected-(U1-SENSOR_VN-Pad5)") (class "Default")
      (node (ref "U1") (pin "5") (pinfunction "SENSOR_VN_5") (pintype "unspecified"))
    )
    (net (code "63") (name "unconnected-(U1-SENSOR_VP-Pad4)") (class "Default")
      (node (ref "U1") (pin "4") (pinfunction "SENSOR_VP_4") (pintype "unspecified"))
    )
    (net (code "64") (name "unconnected-(U2-CTS#-Pad9)") (class "Default")
      (node (ref "U2") (pin "9") (pinfunction "CTS#_9") (pintype "unspecified"))
    )
    (net (code "65") (name "unconnected-(U2-DCD#-Pad12)") (class "Default")
      (node (ref "U2") (pin "12") (pinfunction "DCD#_12") (pintype "unspecified"))
    )
    (net (code "66") (name "unconnected-(U2-DSR#-Pad10)") (class "Default")
      (node (ref "U2") (pin "10") (pinfunction "DSR#_10") (pintype "unspecified"))
    )
    (net (code "67") (name "unconnected-(U2-R232-Pad15)") (class "Default")
      (node (ref "U2") (pin "15") (pinfunction "R232_15") (pintype "unspecified"))
    )
    (net (code "68") (name "unconnected-(U2-RI-Pad11)") (class "Default")
      (node (ref "U2") (pin "11") (pinfunction "RI_11") (pintype "unspecified"))
    )
    (net (code "69") (name "unconnected-(U4-CD-Pad9)") (class "Default")
      (node (ref "U4") (pin "9") (pinfunction "CD_9") (pintype "input"))
    )
    (net (code "70") (name "unconnected-(U4-DAT1(RSV)-Pad8)") (class "Default")
      (node (ref "U4") (pin "8") (pinfunction "DAT1(RSV)_8") (pintype "bidirectional"))
    )
    (net (code "71") (name "unconnected-(U4-DAT2(RSV)-Pad1)") (class "Default")
      (node (ref "U4") (pin "1") (pinfunction "DAT2(RSV)_1") (pintype "bidirectional"))
    )
    (net (code "72") (name "unconnected-(U5-AUX_CL-Pad7)") (class "Default")
      (node (ref "U5") (pin "7") (pinfunction "AUX_CL_7") (pintype "unspecified"))
    )
    (net (code "73") (name "unconnected-(U5-AUX_DA-Pad6)") (class "Default")
      (node (ref "U5") (pin "6") (pinfunction "AUX_DA_6") (pintype "unspecified"))
    )
    (net (code "74") (name "unconnected-(U5-INT-Pad12)") (class "Default")
      (node (ref "U5") (pin "12") (pinfunction "INT_12") (pintype "unspecified"))
    )
    (net (code "75") (name "unconnected-(U5-NC-Pad2)") (class "Default")
      (node (ref "U5") (pin "2") (pinfunction "NC_2") (pintype "unspecified"))
    )
    (net (code "76") (name "unconnected-(U5-NC-Pad3)") (class "Default")
      (node (ref "U5") (pin "3") (pinfunction "NC_3") (pintype "unspecified"))
    )
    (net (code "77") (name "unconnected-(U5-NC-Pad4)") (class "Default")
      (node (ref "U5") (pin "4") (pinfunction "NC_4") (pintype "unspecified"))
    )
    (net (code "78") (name "unconnected-(U5-NC-Pad5)") (class "Default")
      (node (ref "U5") (pin "5") (pinfunction "NC_5") (pintype "unspecified"))
    )
    (net (code "79") (name "unconnected-(U5-NC-Pad14)") (class "Default")
      (node (ref "U5") (pin "14") (pinfunction "NC_14") (pintype "unspecified"))
    )
    (net (code "80") (name "unconnected-(U5-NC-Pad15)") (class "Default")
      (node (ref "U5") (pin "15") (pinfunction "NC_15") (pintype "unspecified"))
    )
    (net (code "81") (name "unconnected-(U5-NC-Pad16)") (class "Default")
      (node (ref "U5") (pin "16") (pinfunction "NC_16") (pintype "unspecified"))
    )
    (net (code "82") (name "unconnected-(U5-NC-Pad17)") (class "Default")
      (node (ref "U5") (pin "17") (pinfunction "NC_17") (pintype "unspecified"))
    )
    (net (code "83") (name "unconnected-(U5-RESV-Pad19)") (class "Default")
      (node (ref "U5") (pin "19") (pinfunction "RESV_19") (pintype "unspecified"))
    )
    (net (code "84") (name "unconnected-(U5-RESV-Pad21)") (class "Default")
      (node (ref "U5") (pin "21") (pinfunction "RESV_21") (pintype "unspecified"))
    )
    (net (code "85") (name "unconnected-(U5-RESV-Pad22)") (class "Default")
      (node (ref "U5") (pin "22") (pinfunction "RESV_22") (pintype "unspecified"))
    )
    (net (code "86") (name "unconnected-(U8-DRDY-Pad15)") (class "Default")
      (node (ref "U8") (pin "15") (pinfunction "DRDY_15") (pintype "unspecified"))
    )
    (net (code "87") (name "unconnected-(U8-NC-Pad3)") (class "Default")
      (node (ref "U8") (pin "3") (pinfunction "NC_3") (pintype "unspecified"))
    )
    (net (code "88") (name "unconnected-(U8-NC-Pad5)") (class "Default")
      (node (ref "U8") (pin "5") (pinfunction "NC_5") (pintype "unspecified"))
    )
    (net (code "89") (name "unconnected-(U8-NC-Pad6)") (class "Default")
      (node (ref "U8") (pin "6") (pinfunction "NC_6") (pintype "unspecified"))
    )
    (net (code "90") (name "unconnected-(U8-NC-Pad7)") (class "Default")
      (node (ref "U8") (pin "7") (pinfunction "NC_7") (pintype "unspecified"))
    )
    (net (code "91") (name "unconnected-(U8-NC-Pad14)") (class "Default")
      (node (ref "U8") (pin "14") (pinfunction "NC_14") (pintype "unspecified"))
    )
    (net (code "92") (name "unconnected-(U9-CSB-Pad1)") (class "Default")
      (node (ref "U9") (pin "1") (pinfunction "CSB_1") (pintype "unspecified"))
    )
    (net (code "93") (name "unconnected-(U9-SDO-Pad4)") (class "Default")
      (node (ref "U9") (pin "4") (pinfunction "SDO_4") (pintype "unspecified"))
    )
    (net (code "94") (name "unconnected-(USB1-EH-Pad6)") (class "Default")
      (node (ref "USB1") (pin "6") (pinfunction "EH_6") (pintype "input"))
    )
    (net (code "95") (name "unconnected-(USB1-ID-Pad4)") (class "Default")
      (node (ref "USB1") (pin "4") (pinfunction "ID_4") (pintype "input"))
    )
  )
)
